# CSAL.net
KiCad netlist of a schematic drawn in Altium Designer
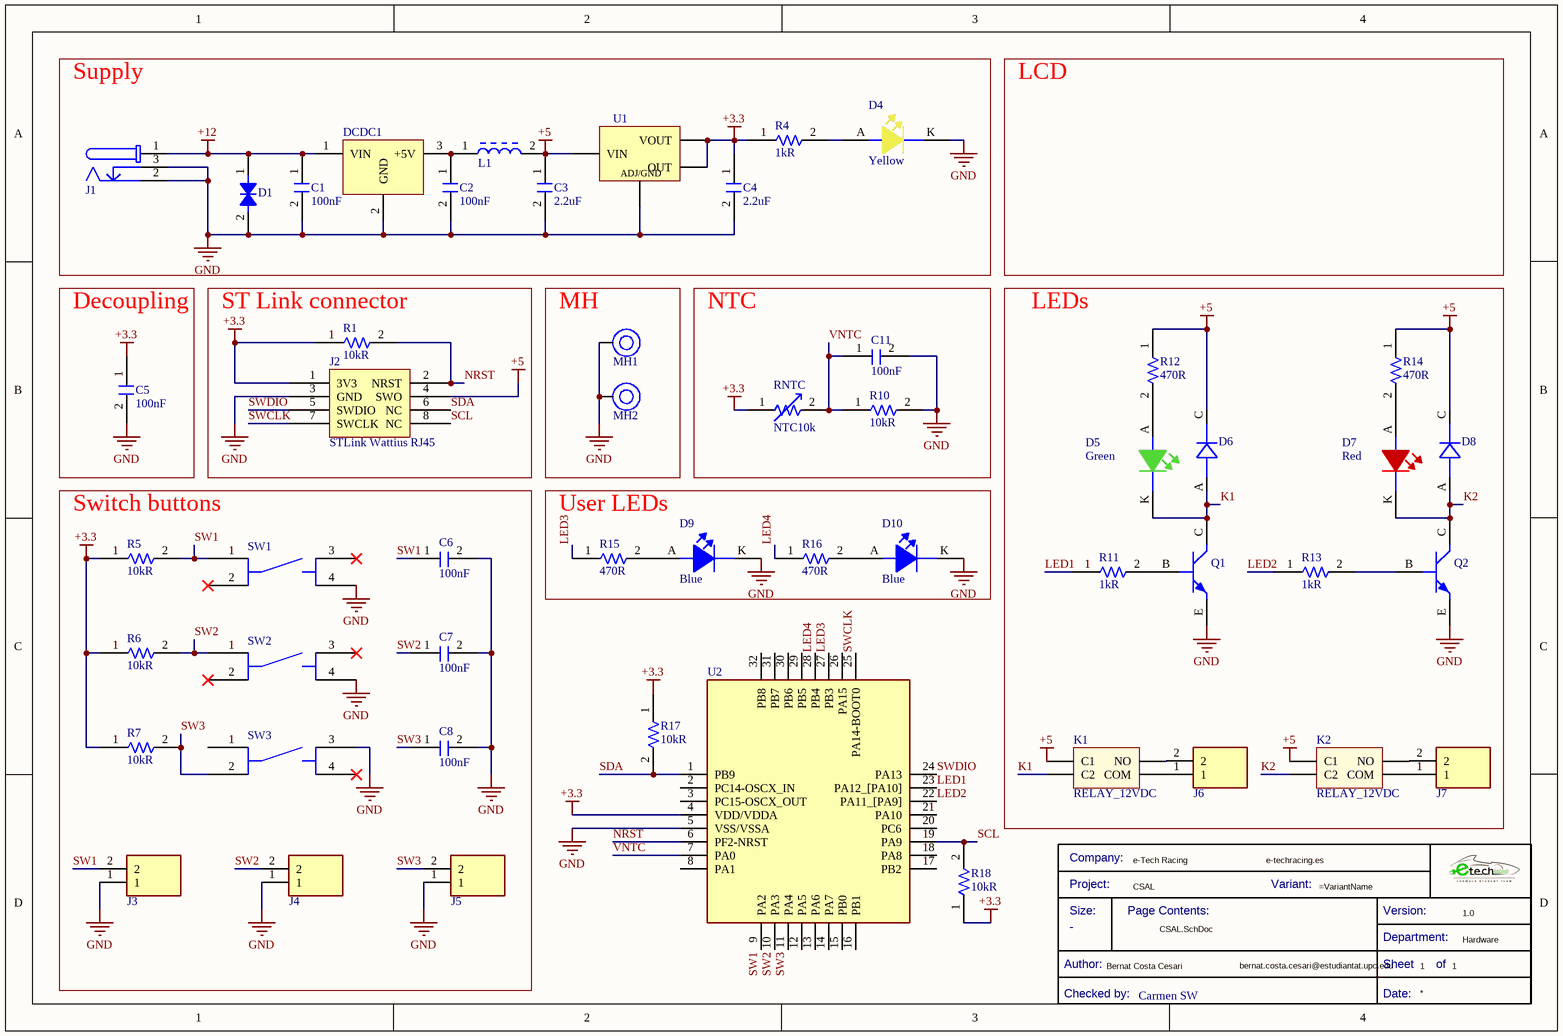
[diagram p0: CSAL.SchDoc]

(export (version "E")
  (design (tool "Eeschema 10.0.6"))
  (components
    (comp (ref "*")
      (value "Title Block_template")
      (description "Standard Title Block")
      (fields
        (field (name "SIZE") "-")
        (field (name ".CREATOR") "GP")
        (field (name ".PCBCHECK") "GP")
        (field (name ".SCHCHECK") "GP")
      )
      (libsource (lib "e-Tech_Racing") (part "Title Block_template"))
    )
    (comp (ref "C1")
      (value "885012207098")
      (footprint "C0805FNPC-R")
      (description "Cap, 0.1ΜF, 50V, 10%, X7R, 0805")
      (fields
        (field (name "TOLERANCE") "10%")
        (field (name "CAPACITANCE") "100nF")
        (field (name ".CREATOR") "DR")
      )
      (libsource (lib "Passives") (part "C100n-50V-0805FNPC-X7R"))
    )
    (comp (ref "C2")
      (value "885012207098")
      (footprint "C0805FNPC-R")
      (description "Cap, 0.1ΜF, 50V, 10%, X7R, 0805")
      (fields
        (field (name "TOLERANCE") "10%")
        (field (name "CAPACITANCE") "100nF")
        (field (name ".CREATOR") "DR")
      )
      (libsource (lib "Passives") (part "C100n-50V-0805FNPC-X7R"))
    )
    (comp (ref "C3")
      (value "2.2uF")
      (footprint "C0805FNPC-W")
      (libsource (lib "Passives") (part "C2.2u-16V-0805FTK"))
    )
    (comp (ref "C4")
      (value "2.2uF")
      (footprint "C0805FNPC-W")
      (libsource (lib "Passives") (part "C2.2u-16V-0805FTK"))
    )
    (comp (ref "C5")
      (value "885012207098")
      (footprint "C0805FNPC-R")
      (description "Cap, 0.1ΜF, 50V, 10%, X7R, 0805")
      (fields
        (field (name "TOLERANCE") "10%")
        (field (name "CAPACITANCE") "100nF")
        (field (name ".CREATOR") "DR")
      )
      (libsource (lib "Passives") (part "C100n-50V-0805FNPC-X7R"))
    )
    (comp (ref "C6")
      (value "885012207098")
      (footprint "C0805FNPC-R")
      (description "Cap, 0.1ΜF, 50V, 10%, X7R, 0805")
      (fields
        (field (name "TOLERANCE") "10%")
        (field (name "CAPACITANCE") "100nF")
        (field (name ".CREATOR") "DR")
      )
      (libsource (lib "Passives") (part "C100n-50V-0805FNPC-X7R"))
    )
    (comp (ref "C7")
      (value "885012207098")
      (footprint "C0805FNPC-R")
      (description "Cap, 0.1ΜF, 50V, 10%, X7R, 0805")
      (fields
        (field (name "TOLERANCE") "10%")
        (field (name "CAPACITANCE") "100nF")
        (field (name ".CREATOR") "DR")
      )
      (libsource (lib "Passives") (part "C100n-50V-0805FNPC-X7R"))
    )
    (comp (ref "C8")
      (value "885012207098")
      (footprint "C0805FNPC-R")
      (description "Cap, 0.1ΜF, 50V, 10%, X7R, 0805")
      (fields
        (field (name "TOLERANCE") "10%")
        (field (name "CAPACITANCE") "100nF")
        (field (name ".CREATOR") "DR")
      )
      (libsource (lib "Passives") (part "C100n-50V-0805FNPC-X7R"))
    )
    (comp (ref "C11")
      (value "885012207098")
      (footprint "C0805FNPC-R")
      (description "Cap, 0.1ΜF, 50V, 10%, X7R, 0805")
      (fields
        (field (name "TOLERANCE") "10%")
        (field (name "CAPACITANCE") "100nF")
        (field (name ".CREATOR") "DR")
      )
      (libsource (lib "Passives") (part "C100n-50V-0805FNPC-X7R"))
    )
    (comp (ref "D1")
      (value "824501261")
      (footprint "DTVS-DO-214AC")
      (description "TVS diode [Würth Elektronik] 824501261 TVS diode")
      (fields (field (name "MANUFACTURER") "Wurth Electronics") (field (name ".CREATOR") "DO"))
      (libsource (lib "Filter components") (part "DTVS-26V-DO-214AC"))
    )
    (comp (ref "D4")
      (value "150120YS75000")
      (footprint "LED_1206_WE")
      (description "Led, Yellow, 590 Nm, 2 V, 30 Ma, 120 Mcd Rohs Compliant: Yes")
      (fields
        (field (name "MANUFACTURER") "Wurth Electronics")
        (field (name "COLOR") "Yellow")
        (field (name ".CREATOR") "GP")
      )
      (libsource (lib "Semiconductor") (part "LEDYS-1206-120"))
    )
    (comp (ref "D5")
      (value "150120GS75000")
      (footprint "LED_1206_WE")
      (description "Led, Green, 520 Nm, 3.2 V, 30 Ma, 450 Mcd Rohs Compliant: Yes")
      (fields
        (field (name "MANUFACTURER") "Wurth Electronics")
        (field (name "COLOR") "Green")
        (field (name ".CREATOR") "GP")
      )
      (libsource (lib "Semiconductor") (part "LEDGS-1206-450"))
    )
    (comp (ref "D6")
      (value "D_THT_1N4004")
      (footprint "D_THT")
      (description "Diode Standard 400V 1A Through Hole DO-41")
      (fields (field (name "MP") "1N4004") (field (name "MF") "ON Semiconductor"))
      (libsource (lib "CommonFiles_Library") (part "D_THT_1N4004"))
    )
    (comp (ref "D7")
      (value "150120RS75000")
      (footprint "LED_1206_WE")
      (description "Led, Red, 625 Nm, 2 V, 30 Ma, 150 Mcd Rohs Compliant: Yes")
      (fields
        (field (name "MANUFACTURER") "Wurth Electronics")
        (field (name "COLOR") "Red")
        (field (name ".CREATOR") "GP")
      )
      (libsource (lib "Semiconductor") (part "LEDRS-1206-150"))
    )
    (comp (ref "D8")
      (value "D_THT_1N4004")
      (footprint "D_THT")
      (description "Diode Standard 400V 1A Through Hole DO-41")
      (fields (field (name "MP") "1N4004") (field (name "MF") "ON Semiconductor"))
      (libsource (lib "CommonFiles_Library") (part "D_THT_1N4004"))
    )
    (comp (ref "D9")
      (value "150120BS75000")
      (footprint "LED_1206_WE")
      (description "Led, Blue, 470 Nm, 3.2 V, 30 Ma, 145 Mcd Rohs Compliant: Yes")
      (fields
        (field (name "MANUFACTURER") "Wurth Electronics")
        (field (name "COLOR") "Blue")
        (field (name ".CREATOR") "GP")
      )
      (libsource (lib "Semiconductor") (part "LEDBS-1206-145"))
    )
    (comp (ref "D10")
      (value "150120BS75000")
      (footprint "LED_1206_WE")
      (description "Led, Blue, 470 Nm, 3.2 V, 30 Ma, 145 Mcd Rohs Compliant: Yes")
      (fields
        (field (name "MANUFACTURER") "Wurth Electronics")
        (field (name "COLOR") "Blue")
        (field (name ".CREATOR") "GP")
      )
      (libsource (lib "Semiconductor") (part "LEDBS-1206-145"))
    )
    (comp (ref "DCDC1")
      (value "173010542")
      (footprint "DCDC_Magi3c")
      (description "Würth Elektronik 8-42V to 5V 1A DC-DC")
      (fields (field (name ".CREATOR") "DR"))
      (libsource (lib "Semiconductor") (part "DCDC-42V/5V-1A"))
    )
    (comp (ref "J1")
      (value "694108301002")
      (footprint "694108301002")
      (description "WR-DC DC Power Jack Connector, Male, Right Angled, 24V, 5A")
      (fields (field (name "MANUFACTURER") "Wurth Elektronik"))
      (libsource (lib "CommonFiles_Library") (part "Supply_Jack_12V"))
    )
    (comp (ref "J2")
      (value "STLink Wattius RJ45")
      (footprint "STLINK_RJ45")
      (libsource (lib "Electromechanical") (part "STLink_Wattius_RJ45_Adapter"))
    )
    (comp (ref "J3")
      (value "J_2_CableContact")
      (footprint "TE_282834-2")
      (fields (field (name "MP") "282834-2") (field (name "MF") "{'manufacturer': u'TE Connectivity'}"))
      (libsource (lib "CommonFiles_Library") (part "J_2_CableContact"))
    )
    (comp (ref "J4")
      (value "J_2_CableContact")
      (footprint "TE_282834-2")
      (fields (field (name "MP") "282834-2") (field (name "MF") "{'manufacturer': u'TE Connectivity'}"))
      (libsource (lib "CommonFiles_Library") (part "J_2_CableContact"))
    )
    (comp (ref "J5")
      (value "J_2_CableContact")
      (footprint "TE_282834-2")
      (fields (field (name "MP") "282834-2") (field (name "MF") "{'manufacturer': u'TE Connectivity'}"))
      (libsource (lib "CommonFiles_Library") (part "J_2_CableContact"))
    )
    (comp (ref "J6")
      (value "J_2_CableContact")
      (footprint "TE_282834-2")
      (fields (field (name "MP") "282834-2") (field (name "MF") "{'manufacturer': u'TE Connectivity'}"))
      (libsource (lib "CommonFiles_Library") (part "J_2_CableContact"))
    )
    (comp (ref "J7")
      (value "J_2_CableContact")
      (footprint "TE_282834-2")
      (fields (field (name "MP") "282834-2") (field (name "MF") "{'manufacturer': u'TE Connectivity'}"))
      (libsource (lib "CommonFiles_Library") (part "J_2_CableContact"))
    )
    (comp (ref "K1")
      (value "RELAY_12VDC")
      (footprint "RELAY_ALQ305")
      (libsource (lib "CommonFiles_Library") (part "RELAY_12VDC"))
    )
    (comp (ref "K2")
      (value "RELAY_12VDC")
      (footprint "RELAY_ALQ305")
      (libsource (lib "CommonFiles_Library") (part "RELAY_12VDC"))
    )
    (comp (ref "L1")
      (value "BLM18EG331TN1D")
      (footprint "L_Ferrite_Bead_0805")
      (description "Ferrite Beads Multi-Layer 330Ohm 25% 100MHz 500mA 210mOhm DCR 0603 Paper T/R")
      (fields
        (field (name "MANUFACTURER") "Murata")
        (field (name "TOLERANCE") "25%")
        (field (name ".CREATOR") "GP")
      )
      (libsource (lib "Filter components") (part "L_Ferrite_bead_BLM18EG331TN1D"))
    )
    (comp (ref "MH1")
      (value "Mounting_Hole_M3")
      (footprint "Mounting_Hole_M3")
      (libsource (lib "Electromechanical") (part "Mounting_Hole_M3"))
    )
    (comp (ref "MH2")
      (value "Mounting_Hole_M3")
      (footprint "Mounting_Hole_M3")
      (libsource (lib "Electromechanical") (part "Mounting_Hole_M3"))
    )
    (comp (ref "Q1")
      (value "BC817-25LT1G")
      (footprint "TRT-NPN-0.5/45-SOT23")
      (description "ON Semi BC817-25LT1G NPN Bipolar Transistor; 0.5 A; 45 V; 3-Pin SOT-23")
      (fields (field (name ".CREATOR") "GP"))
      (libsource (lib "Semiconductor") (part "TRT-NPN-0.5/45-SOT23"))
    )
    (comp (ref "Q2")
      (value "BC817-25LT1G")
      (footprint "TRT-NPN-0.5/45-SOT23")
      (description "ON Semi BC817-25LT1G NPN Bipolar Transistor; 0.5 A; 45 V; 3-Pin SOT-23")
      (fields (field (name ".CREATOR") "GP"))
      (libsource (lib "Semiconductor") (part "TRT-NPN-0.5/45-SOT23"))
    )
    (comp (ref "R1")
      (value "CR0805-JW-103ELF")
      (footprint "R0805FTK")
      (fields
        (field (name "TOLERANCE") "5%")
        (field (name "RESISTANCE") "10kR")
        (field (name ".CREATOR") "DR")
      )
      (libsource (lib "Passives") (part "R10k-0805FTK"))
    )
    (comp (ref "R4")
      (value "CR0805-JW-102ELF")
      (footprint "R0805FTK")
      (description "Res Thick Film 0805 1K Ohm 5% 1/8W ±200ppm/°C Molded SMD SMD Paper Tape on Plastic Reel")
      (fields
        (field (name "TOLERANCE") "5%")
        (field (name "RESISTANCE") "1kR")
        (field (name ".CREATOR") "GP")
      )
      (libsource (lib "Passives") (part "R1k-0805FTK"))
    )
    (comp (ref "R5")
      (value "CR0805-JW-103ELF")
      (footprint "R0805FTK")
      (fields
        (field (name "TOLERANCE") "5%")
        (field (name "RESISTANCE") "10kR")
        (field (name ".CREATOR") "DR")
      )
      (libsource (lib "Passives") (part "R10k-0805FTK"))
    )
    (comp (ref "R6")
      (value "CR0805-JW-103ELF")
      (footprint "R0805FTK")
      (fields
        (field (name "TOLERANCE") "5%")
        (field (name "RESISTANCE") "10kR")
        (field (name ".CREATOR") "DR")
      )
      (libsource (lib "Passives") (part "R10k-0805FTK"))
    )
    (comp (ref "R7")
      (value "CR0805-JW-103ELF")
      (footprint "R0805FTK")
      (fields
        (field (name "TOLERANCE") "5%")
        (field (name "RESISTANCE") "10kR")
        (field (name ".CREATOR") "DR")
      )
      (libsource (lib "Passives") (part "R10k-0805FTK"))
    )
    (comp (ref "R10")
      (value "CR0805-JW-103ELF")
      (footprint "R0805FTK")
      (fields
        (field (name "TOLERANCE") "5%")
        (field (name "RESISTANCE") "10kR")
        (field (name ".CREATOR") "DR")
      )
      (libsource (lib "Passives") (part "R10k-0805FTK"))
    )
    (comp (ref "R11")
      (value "CR0805-JW-102ELF")
      (footprint "R0805FTK")
      (description "Res Thick Film 0805 1K Ohm 5% 1/8W ±200ppm/°C Molded SMD SMD Paper Tape on Plastic Reel")
      (fields
        (field (name "TOLERANCE") "5%")
        (field (name "RESISTANCE") "1kR")
        (field (name ".CREATOR") "GP")
      )
      (libsource (lib "Passives") (part "R1k-0805FTK"))
    )
    (comp (ref "R12")
      (value "CR0805-FX-4700GLF")
      (footprint "R0805FTK")
      (description "Res Thick Film 0805 470 Ohm 1% 1/8W ±100ppm/°C Molded SMD SMD Paper Tape on Plastic Reel")
      (fields
        (field (name "TOLERANCE") "1%")
        (field (name "RESISTANCE") "470R")
        (field (name ".CREATOR") "DR")
      )
      (libsource (lib "Passives") (part "R470-0805FTK"))
    )
    (comp (ref "R13")
      (value "CR0805-JW-102ELF")
      (footprint "R0805FTK")
      (description "Res Thick Film 0805 1K Ohm 5% 1/8W ±200ppm/°C Molded SMD SMD Paper Tape on Plastic Reel")
      (fields
        (field (name "TOLERANCE") "5%")
        (field (name "RESISTANCE") "1kR")
        (field (name ".CREATOR") "GP")
      )
      (libsource (lib "Passives") (part "R1k-0805FTK"))
    )
    (comp (ref "R14")
      (value "CR0805-FX-4700GLF")
      (footprint "R0805FTK")
      (description "Res Thick Film 0805 470 Ohm 1% 1/8W ±100ppm/°C Molded SMD SMD Paper Tape on Plastic Reel")
      (fields
        (field (name "TOLERANCE") "1%")
        (field (name "RESISTANCE") "470R")
        (field (name ".CREATOR") "DR")
      )
      (libsource (lib "Passives") (part "R470-0805FTK"))
    )
    (comp (ref "R15")
      (value "CR0805-FX-4700GLF")
      (footprint "R0805FTK")
      (description "Res Thick Film 0805 470 Ohm 1% 1/8W ±100ppm/°C Molded SMD SMD Paper Tape on Plastic Reel")
      (fields
        (field (name "TOLERANCE") "1%")
        (field (name "RESISTANCE") "470R")
        (field (name ".CREATOR") "DR")
      )
      (libsource (lib "Passives") (part "R470-0805FTK"))
    )
    (comp (ref "R16")
      (value "CR0805-FX-4700GLF")
      (footprint "R0805FTK")
      (description "Res Thick Film 0805 470 Ohm 1% 1/8W ±100ppm/°C Molded SMD SMD Paper Tape on Plastic Reel")
      (fields
        (field (name "TOLERANCE") "1%")
        (field (name "RESISTANCE") "470R")
        (field (name ".CREATOR") "DR")
      )
      (libsource (lib "Passives") (part "R470-0805FTK"))
    )
    (comp (ref "R17")
      (value "CR0805-JW-103ELF")
      (footprint "R0805FTK")
      (fields
        (field (name "TOLERANCE") "5%")
        (field (name "RESISTANCE") "10kR")
        (field (name ".CREATOR") "DR")
      )
      (libsource (lib "Passives") (part "R10k-0805FTK"))
    )
    (comp (ref "R18")
      (value "CR0805-JW-103ELF")
      (footprint "R0805FTK")
      (fields
        (field (name "TOLERANCE") "5%")
        (field (name "RESISTANCE") "10kR")
        (field (name ".CREATOR") "DR")
      )
      (libsource (lib "Passives") (part "R10k-0805FTK"))
    )
    (comp (ref "RNTC")
      (value "NTC10k")
      (footprint "NTC10k_0805")
      (libsource (lib "CommonFiles_Library") (part "NTC_10k_0805"))
    )
    (comp (ref "SW1")
      (value "Tactile SW")
      (footprint "SW_2-1437565-7")
      (libsource (lib "CommonFiles_Library") (part "SW_6x6"))
    )
    (comp (ref "SW2")
      (value "Tactile SW")
      (footprint "SW_2-1437565-7")
      (libsource (lib "CommonFiles_Library") (part "SW_6x6"))
    )
    (comp (ref "SW3")
      (value "Tactile SW")
      (footprint "SW_2-1437565-7")
      (libsource (lib "CommonFiles_Library") (part "SW_6x6"))
    )
    (comp (ref "U1")
      (value "LM1117IMP-3.3/NOPB")
      (footprint "LDO_10V-0.8/3V3-SOT223")
      (description "LDO Regulator Pos 3.3V 0.8A 4-Pin(3+Tab) SOT-223 T/R / IC REG LDO 3.3V 0.8A SOT223")
      (fields (field (name "MANUFACTURER") "Texas Instruments") (field (name ".CREATOR") "GP"))
      (libsource (lib "Semiconductor") (part "LDO_10V-0.8/3V3-SOT223"))
    )
    (comp (ref "U2")
      (value "STM32C031K4T6")
      (footprint "QFP80P900X900X160-32N")
      (fields (field (name "MOUSER PART NUMBER") "511-STM32C031K4T6"))
      (libsource (lib "CommonFiles_Library") (part "STM32C031K4T6"))
    )
  )
  (nets
    (net (code "1") (name "+3.3") (class "Default")
      (node (ref "C4") (pin "1") (pinfunction "1_1") (pintype "passive"))
      (node (ref "C5") (pin "1") (pinfunction "1_1") (pintype "passive"))
      (node (ref "J2") (pin "1") (pinfunction "3V3_1") (pintype "passive"))
      (node (ref "R1") (pin "1") (pinfunction "1_1") (pintype "passive"))
      (node (ref "R17") (pin "1") (pinfunction "1_1") (pintype "passive"))
      (node (ref "R18") (pin "1") (pinfunction "1_1") (pintype "passive"))
      (node (ref "R4") (pin "1") (pinfunction "1_1") (pintype "passive"))
      (node (ref "R5") (pin "1") (pinfunction "1_1") (pintype "passive"))
      (node (ref "R6") (pin "1") (pinfunction "1_1") (pintype "passive"))
      (node (ref "R7") (pin "1") (pinfunction "1_1") (pintype "passive"))
      (node (ref "RNTC") (pin "1") (pinfunction "2_1") (pintype "passive"))
      (node (ref "U1") (pin "2") (pinfunction "OUT_2") (pintype "passive"))
      (node (ref "U1") (pin "4") (pinfunction "VOUT_4") (pintype "passive"))
      (node (ref "U2") (pin "4") (pinfunction "VDD/VDDA_4") (pintype "passive"))
    )
    (net (code "2") (name "+5") (class "Default")
      (node (ref "C3") (pin "1") (pinfunction "1_1") (pintype "passive"))
      (node (ref "D6") (pin "C") (pinfunction "C_C") (pintype "passive"))
      (node (ref "D8") (pin "C") (pinfunction "C_C") (pintype "passive"))
      (node (ref "J2") (pin "4") (pinfunction "SWO_4") (pintype "passive"))
      (node (ref "K1") (pin "C1") (pinfunction "C1_C1") (pintype "passive"))
      (node (ref "K2") (pin "C1") (pinfunction "C1_C1") (pintype "passive"))
      (node (ref "L1") (pin "2") (pinfunction "2_2") (pintype "passive"))
      (node (ref "R12") (pin "1") (pinfunction "1_1") (pintype "passive"))
      (node (ref "R14") (pin "1") (pinfunction "1_1") (pintype "passive"))
      (node (ref "U1") (pin "3") (pinfunction "VIN_3") (pintype "passive"))
    )
    (net (code "3") (name "+12") (class "Default")
      (node (ref "C1") (pin "1") (pinfunction "1_1") (pintype "passive"))
      (node (ref "D1") (pin "1") (pinfunction "1_1") (pintype "passive"))
      (node (ref "DCDC1") (pin "1") (pinfunction "VIN_1") (pintype "passive"))
      (node (ref "J1") (pin "1") (pinfunction "1_1") (pintype "passive"))
    )
    (net (code "4") (name "/K1") (class "Default")
      (node (ref "D5") (pin "K") (pinfunction "K_K") (pintype "passive"))
      (node (ref "D6") (pin "A") (pinfunction "A_A") (pintype "passive"))
      (node (ref "K1") (pin "C2") (pinfunction "C2_C2") (pintype "passive"))
      (node (ref "Q1") (pin "C") (pinfunction "C_C") (pintype "passive"))
    )
    (net (code "5") (name "/K2") (class "Default")
      (node (ref "D7") (pin "K") (pinfunction "K_K") (pintype "passive"))
      (node (ref "D8") (pin "A") (pinfunction "A_A") (pintype "passive"))
      (node (ref "K2") (pin "C2") (pinfunction "C2_C2") (pintype "passive"))
      (node (ref "Q2") (pin "C") (pinfunction "C_C") (pintype "passive"))
    )
    (net (code "6") (name "/LED1") (class "Default")
      (node (ref "R11") (pin "1") (pinfunction "1_1") (pintype "passive"))
      (node (ref "U2") (pin "23") (pinfunction "PA12_[PA10]_23") (pintype "passive"))
    )
    (net (code "7") (name "/LED2") (class "Default")
      (node (ref "R13") (pin "1") (pinfunction "1_1") (pintype "passive"))
      (node (ref "U2") (pin "22") (pinfunction "PA11_[PA9]_22") (pintype "passive"))
    )
    (net (code "8") (name "/LED3") (class "Default")
      (node (ref "R15") (pin "1") (pinfunction "1_1") (pintype "passive"))
      (node (ref "U2") (pin "27") (pinfunction "PB3_27") (pintype "passive"))
    )
    (net (code "9") (name "/LED4") (class "Default")
      (node (ref "R16") (pin "1") (pinfunction "1_1") (pintype "passive"))
      (node (ref "U2") (pin "28") (pinfunction "PB4_28") (pintype "passive"))
    )
    (net (code "10") (name "/NRST") (class "Default")
      (node (ref "J2") (pin "2") (pinfunction "NRST_2") (pintype "passive"))
      (node (ref "R1") (pin "2") (pinfunction "2_2") (pintype "passive"))
      (node (ref "U2") (pin "6") (pinfunction "PF2-NRST_6") (pintype "passive"))
    )
    (net (code "11") (name "/SCL") (class "Default")
      (node (ref "J2") (pin "8") (pinfunction "NC_8") (pintype "passive"))
      (node (ref "R18") (pin "2") (pinfunction "2_2") (pintype "passive"))
      (node (ref "U2") (pin "19") (pinfunction "PA9_19") (pintype "passive"))
    )
    (net (code "12") (name "/SDA") (class "Default")
      (node (ref "J2") (pin "6") (pinfunction "NC_6") (pintype "passive"))
      (node (ref "R17") (pin "2") (pinfunction "2_2") (pintype "passive"))
      (node (ref "U2") (pin "1") (pinfunction "PB9_1") (pintype "passive"))
    )
    (net (code "13") (name "/SW1") (class "Default")
      (node (ref "C6") (pin "1") (pinfunction "1_1") (pintype "passive"))
      (node (ref "J3") (pin "2") (pinfunction "2_2") (pintype "passive"))
      (node (ref "R5") (pin "2") (pinfunction "2_2") (pintype "passive"))
      (node (ref "SW1") (pin "1") (pinfunction "1_1") (pintype "passive"))
    )
    (net (code "14") (name "/SW2") (class "Default")
      (node (ref "C7") (pin "1") (pinfunction "1_1") (pintype "passive"))
      (node (ref "J4") (pin "2") (pinfunction "2_2") (pintype "passive"))
      (node (ref "R6") (pin "2") (pinfunction "2_2") (pintype "passive"))
      (node (ref "SW2") (pin "1") (pinfunction "1_1") (pintype "passive"))
    )
    (net (code "15") (name "/SW3") (class "Default")
      (node (ref "C8") (pin "1") (pinfunction "1_1") (pintype "passive"))
      (node (ref "J5") (pin "2") (pinfunction "2_2") (pintype "passive"))
      (node (ref "R7") (pin "2") (pinfunction "2_2") (pintype "passive"))
      (node (ref "SW3") (pin "2") (pinfunction "2_2") (pintype "passive"))
    )
    (net (code "16") (name "/SWCLK") (class "Default")
      (node (ref "J2") (pin "7") (pinfunction "SWCLK_7") (pintype "passive"))
      (node (ref "U2") (pin "25") (pinfunction "PA14-BOOT0_25") (pintype "passive"))
    )
    (net (code "17") (name "/SWDIO") (class "Default")
      (node (ref "J2") (pin "5") (pinfunction "SWDIO_5") (pintype "passive"))
      (node (ref "U2") (pin "24") (pinfunction "PA13_24") (pintype "passive"))
    )
    (net (code "18") (name "/VNTC") (class "Default")
      (node (ref "C11") (pin "1") (pinfunction "1_1") (pintype "passive"))
      (node (ref "R10") (pin "1") (pinfunction "1_1") (pintype "passive"))
      (node (ref "RNTC") (pin "2") (pinfunction "2_2") (pintype "passive"))
      (node (ref "U2") (pin "7") (pinfunction "PA0_7") (pintype "passive"))
    )
    (net (code "19") (name "GND") (class "Default")
      (node (ref "C1") (pin "2") (pinfunction "2_2") (pintype "passive"))
      (node (ref "C11") (pin "2") (pinfunction "2_2") (pintype "passive"))
      (node (ref "C2") (pin "2") (pinfunction "2_2") (pintype "passive"))
      (node (ref "C3") (pin "2") (pinfunction "2_2") (pintype "passive"))
      (node (ref "C4") (pin "2") (pinfunction "2_2") (pintype "passive"))
      (node (ref "C5") (pin "2") (pinfunction "2_2") (pintype "passive"))
      (node (ref "C6") (pin "2") (pinfunction "2_2") (pintype "passive"))
      (node (ref "C7") (pin "2") (pinfunction "2_2") (pintype "passive"))
      (node (ref "C8") (pin "2") (pinfunction "2_2") (pintype "passive"))
      (node (ref "D1") (pin "2") (pinfunction "2_2") (pintype "passive"))
      (node (ref "D10") (pin "K") (pinfunction "K_K") (pintype "passive"))
      (node (ref "D4") (pin "K") (pinfunction "K_K") (pintype "passive"))
      (node (ref "D9") (pin "K") (pinfunction "K_K") (pintype "passive"))
      (node (ref "DCDC1") (pin "2") (pinfunction "GND_2") (pintype "passive"))
      (node (ref "J1") (pin "2") (pinfunction "2_2") (pintype "passive"))
      (node (ref "J1") (pin "3") (pinfunction "3_3") (pintype "passive"))
      (node (ref "J2") (pin "3") (pinfunction "GND_3") (pintype "passive"))
      (node (ref "J3") (pin "1") (pinfunction "1_1") (pintype "passive"))
      (node (ref "J4") (pin "1") (pinfunction "1_1") (pintype "passive"))
      (node (ref "J5") (pin "1") (pinfunction "1_1") (pintype "passive"))
      (node (ref "MH1") (pin "1") (pinfunction "1_1") (pintype "passive"))
      (node (ref "MH2") (pin "1") (pinfunction "1_1") (pintype "passive"))
      (node (ref "Q1") (pin "E") (pinfunction "E_E") (pintype "passive"))
      (node (ref "Q2") (pin "E") (pinfunction "E_E") (pintype "passive"))
      (node (ref "R10") (pin "2") (pinfunction "2_2") (pintype "passive"))
      (node (ref "SW1") (pin "4") (pinfunction "4_4") (pintype "passive"))
      (node (ref "SW2") (pin "4") (pinfunction "4_4") (pintype "passive"))
      (node (ref "SW3") (pin "3") (pinfunction "3_3") (pintype "passive"))
      (node (ref "U1") (pin "1") (pinfunction "ADJ/GND_1") (pintype "passive"))
      (node (ref "U2") (pin "5") (pinfunction "VSS/VSSA_5") (pintype "passive"))
    )
    (net (code "20") (name "Net-(D4-PadA)") (class "Default")
      (node (ref "D4") (pin "A") (pinfunction "A_A") (pintype "passive"))
      (node (ref "R4") (pin "2") (pinfunction "2_2") (pintype "passive"))
    )
    (net (code "21") (name "Net-(D5-PadA)") (class "Default")
      (node (ref "D5") (pin "A") (pinfunction "A_A") (pintype "passive"))
      (node (ref "R12") (pin "2") (pinfunction "2_2") (pintype "passive"))
    )
    (net (code "22") (name "Net-(D7-PadA)") (class "Default")
      (node (ref "D7") (pin "A") (pinfunction "A_A") (pintype "passive"))
      (node (ref "R14") (pin "2") (pinfunction "2_2") (pintype "passive"))
    )
    (net (code "23") (name "Net-(D9-PadA)") (class "Default")
      (node (ref "D9") (pin "A") (pinfunction "A_A") (pintype "passive"))
      (node (ref "R15") (pin "2") (pinfunction "2_2") (pintype "passive"))
    )
    (net (code "24") (name "Net-(D10-PadA)") (class "Default")
      (node (ref "D10") (pin "A") (pinfunction "A_A") (pintype "passive"))
      (node (ref "R16") (pin "2") (pinfunction "2_2") (pintype "passive"))
    )
    (net (code "25") (name "Net-(DCDC1-+5V)") (class "Default")
      (node (ref "C2") (pin "1") (pinfunction "1_1") (pintype "passive"))
      (node (ref "DCDC1") (pin "3") (pinfunction "+5V_3") (pintype "passive"))
      (node (ref "L1") (pin "1") (pinfunction "1_1") (pintype "passive"))
    )
    (net (code "26") (name "Net-(J6-Pad1)") (class "Default")
      (node (ref "J6") (pin "1") (pinfunction "1_1") (pintype "passive"))
      (node (ref "K1") (pin "COM") (pinfunction "COM_COM") (pintype "passive"))
    )
    (net (code "27") (name "Net-(J6-Pad2)") (class "Default")
      (node (ref "J6") (pin "2") (pinfunction "2_2") (pintype "passive"))
      (node (ref "K1") (pin "NO") (pinfunction "NO_NO") (pintype "passive"))
    )
    (net (code "28") (name "Net-(J7-Pad1)") (class "Default")
      (node (ref "J7") (pin "1") (pinfunction "1_1") (pintype "passive"))
      (node (ref "K2") (pin "COM") (pinfunction "COM_COM") (pintype "passive"))
    )
    (net (code "29") (name "Net-(J7-Pad2)") (class "Default")
      (node (ref "J7") (pin "2") (pinfunction "2_2") (pintype "passive"))
      (node (ref "K2") (pin "NO") (pinfunction "NO_NO") (pintype "passive"))
    )
    (net (code "30") (name "Net-(Q1-PadB)") (class "Default")
      (node (ref "Q1") (pin "B") (pinfunction "B_B") (pintype "passive"))
      (node (ref "R11") (pin "2") (pinfunction "2_2") (pintype "passive"))
    )
    (net (code "31") (name "Net-(Q2-PadB)") (class "Default")
      (node (ref "Q2") (pin "B") (pinfunction "B_B") (pintype "passive"))
      (node (ref "R13") (pin "2") (pinfunction "2_2") (pintype "passive"))
    )
    (net (code "32") (name "unconnected-(SW1-Pad2)") (class "Default")
      (node (ref "SW1") (pin "2") (pinfunction "2_2") (pintype "passive+no_connect"))
    )
    (net (code "33") (name "unconnected-(SW1-Pad3)") (class "Default")
      (node (ref "SW1") (pin "3") (pinfunction "3_3") (pintype "passive+no_connect"))
    )
    (net (code "34") (name "unconnected-(SW2-Pad2)") (class "Default")
      (node (ref "SW2") (pin "2") (pinfunction "2_2") (pintype "passive+no_connect"))
    )
    (net (code "35") (name "unconnected-(SW2-Pad3)") (class "Default")
      (node (ref "SW2") (pin "3") (pinfunction "3_3") (pintype "passive+no_connect"))
    )
    (net (code "36") (name "unconnected-(SW3-Pad1)") (class "Default")
      (node (ref "SW3") (pin "1") (pinfunction "1_1") (pintype "passive"))
    )
    (net (code "37") (name "unconnected-(SW3-Pad4)") (class "Default")
      (node (ref "SW3") (pin "4") (pinfunction "4_4") (pintype "passive+no_connect"))
    )
    (net (code "38") (name "unconnected-(U2-PA1-Pad8)") (class "Default")
      (node (ref "U2") (pin "8") (pinfunction "PA1_8") (pintype "passive"))
    )
    (net (code "39") (name "unconnected-(U2-PA2-Pad9)") (class "Default")
      (node (ref "U2") (pin "9") (pinfunction "PA2_9") (pintype "passive"))
    )
    (net (code "40") (name "unconnected-(U2-PA3-Pad10)") (class "Default")
      (node (ref "U2") (pin "10") (pinfunction "PA3_10") (pintype "passive"))
    )
    (net (code "41") (name "unconnected-(U2-PA4-Pad11)") (class "Default")
      (node (ref "U2") (pin "11") (pinfunction "PA4_11") (pintype "passive"))
    )
    (net (code "42") (name "unconnected-(U2-PA5-Pad12)") (class "Default")
      (node (ref "U2") (pin "12") (pinfunction "PA5_12") (pintype "passive"))
    )
    (net (code "43") (name "unconnected-(U2-PA6-Pad13)") (class "Default")
      (node (ref "U2") (pin "13") (pinfunction "PA6_13") (pintype "passive"))
    )
    (net (code "44") (name "unconnected-(U2-PA7-Pad14)") (class "Default")
      (node (ref "U2") (pin "14") (pinfunction "PA7_14") (pintype "passive"))
    )
    (net (code "45") (name "unconnected-(U2-PA8-Pad18)") (class "Default")
      (node (ref "U2") (pin "18") (pinfunction "PA8_18") (pintype "passive"))
    )
    (net (code "46") (name "unconnected-(U2-PA10-Pad21)") (class "Default")
      (node (ref "U2") (pin "21") (pinfunction "PA10_21") (pintype "passive"))
    )
    (net (code "47") (name "unconnected-(U2-PA15-Pad26)") (class "Default")
      (node (ref "U2") (pin "26") (pinfunction "PA15_26") (pintype "passive"))
    )
    (net (code "48") (name "unconnected-(U2-PB0-Pad15)") (class "Default")
      (node (ref "U2") (pin "15") (pinfunction "PB0_15") (pintype "passive"))
    )
    (net (code "49") (name "unconnected-(U2-PB1-Pad16)") (class "Default")
      (node (ref "U2") (pin "16") (pinfunction "PB1_16") (pintype "passive"))
    )
    (net (code "50") (name "unconnected-(U2-PB2-Pad17)") (class "Default")
      (node (ref "U2") (pin "17") (pinfunction "PB2_17") (pintype "passive"))
    )
    (net (code "51") (name "unconnected-(U2-PB5-Pad29)") (class "Default")
      (node (ref "U2") (pin "29") (pinfunction "PB5_29") (pintype "passive"))
    )
    (net (code "52") (name "unconnected-(U2-PB6-Pad30)") (class "Default")
      (node (ref "U2") (pin "30") (pinfunction "PB6_30") (pintype "passive"))
    )
    (net (code "53") (name "unconnected-(U2-PB7-Pad31)") (class "Default")
      (node (ref "U2") (pin "31") (pinfunction "PB7_31") (pintype "passive"))
    )
    (net (code "54") (name "unconnected-(U2-PB8-Pad32)") (class "Default")
      (node (ref "U2") (pin "32") (pinfunction "PB8_32") (pintype "passive"))
    )
    (net (code "55") (name "unconnected-(U2-PC6-Pad20)") (class "Default")
      (node (ref "U2") (pin "20") (pinfunction "PC6_20") (pintype "passive"))
    )
    (net (code "56") (name "unconnected-(U2-PC14-OSCX_IN-Pad2)") (class "Default")
      (node (ref "U2") (pin "2") (pinfunction "PC14-OSCX_IN_2") (pintype "passive"))
    )
    (net (code "57") (name "unconnected-(U2-PC15-OSCX_OUT-Pad3)") (class "Default")
      (node (ref "U2") (pin "3") (pinfunction "PC15-OSCX_OUT_3") (pintype "passive"))
    )
  )
)
